# 10-RJ45_Protection.net
KiCad netlist of a schematic drawn in Altium Designer
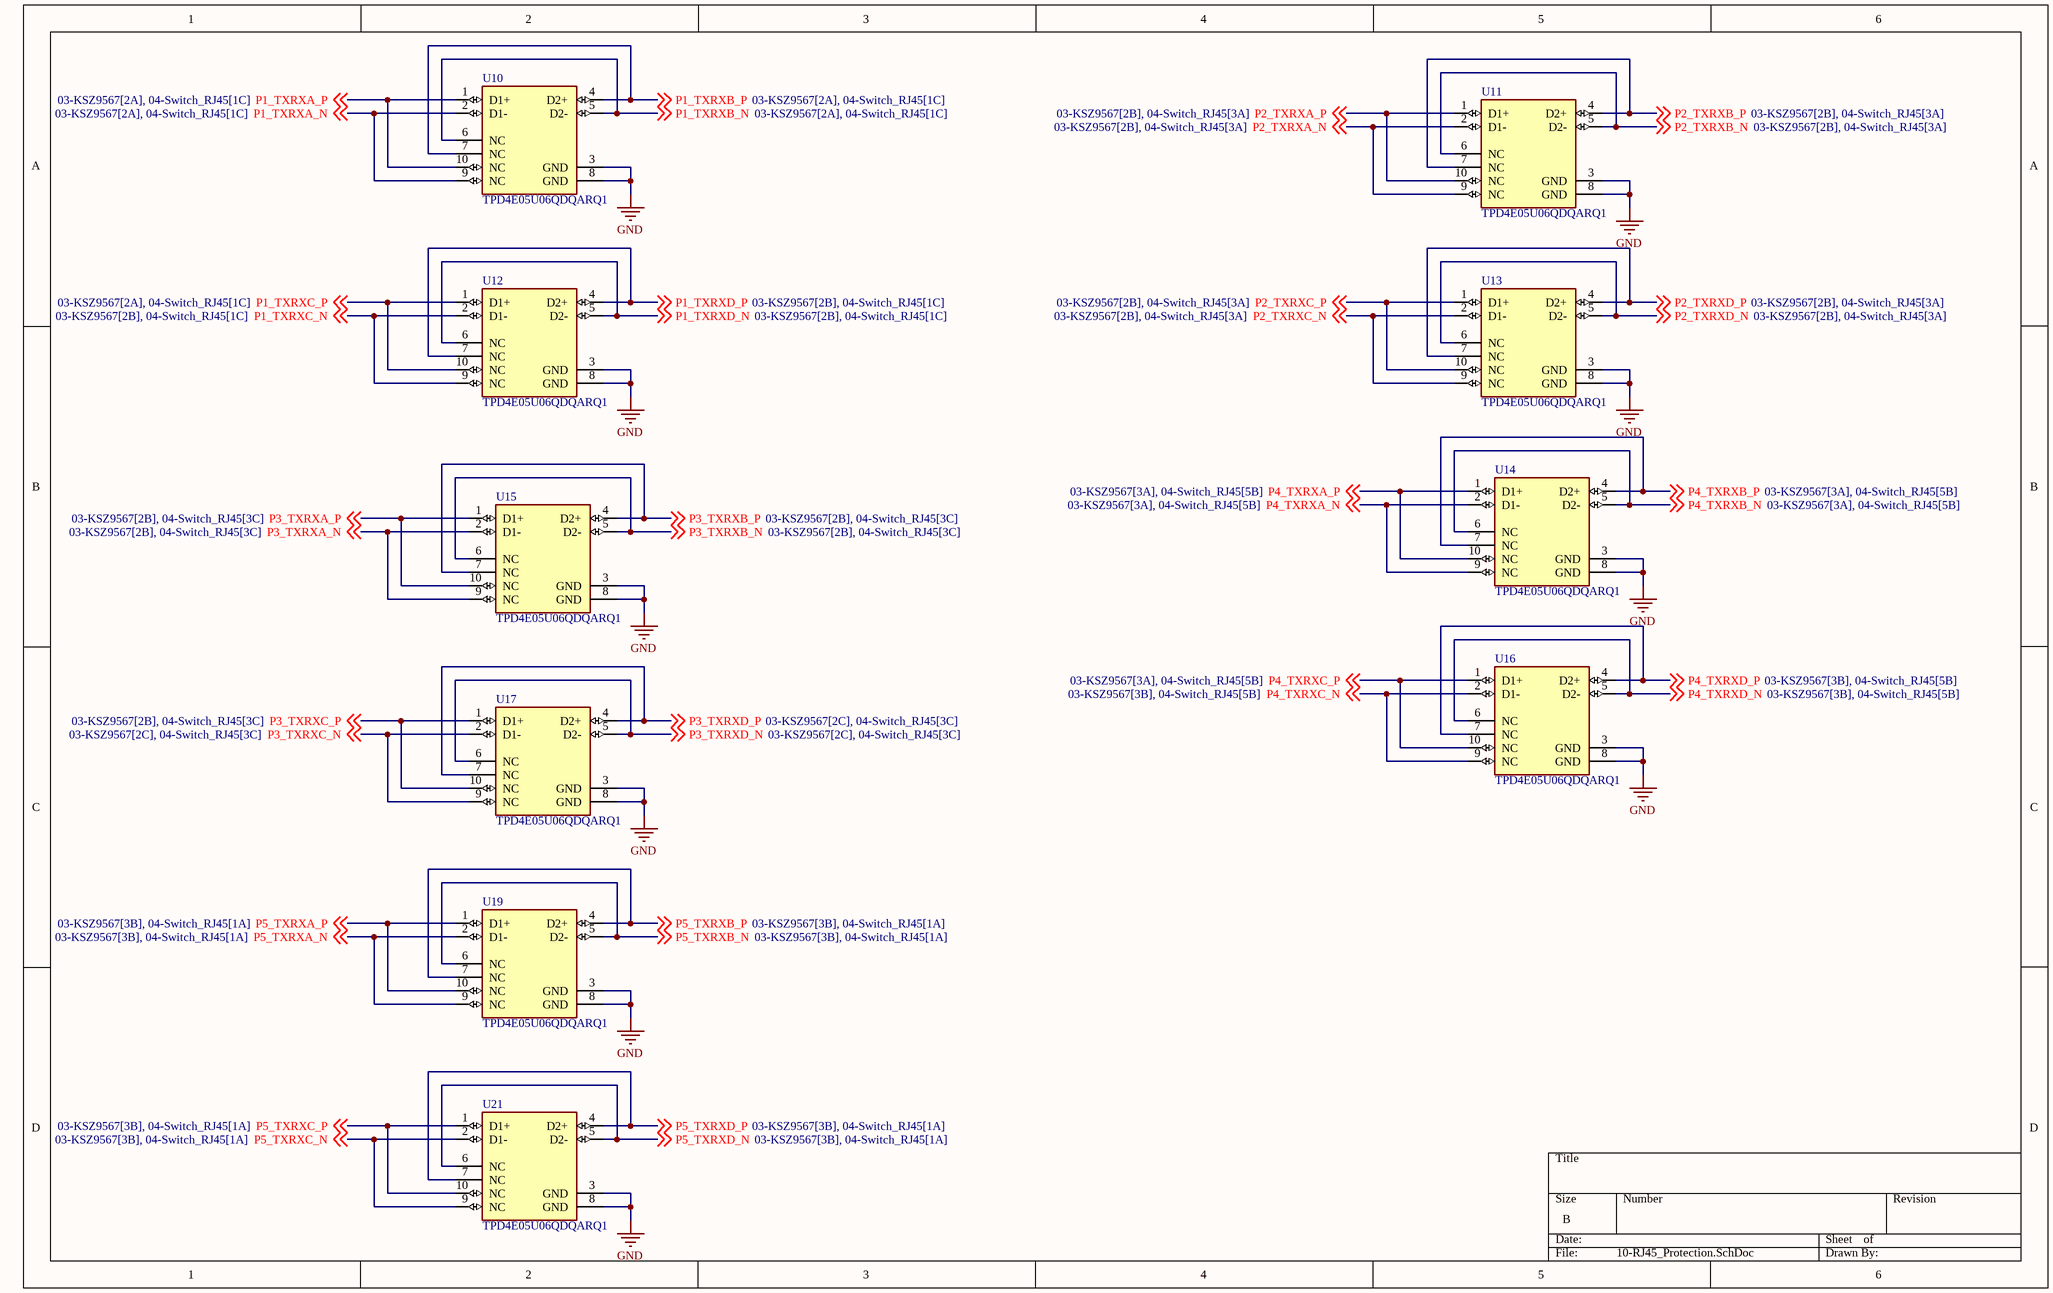
[diagram p0: 10-RJ45_Protection.SchDoc]

(export (version "E")
  (design (tool "Eeschema 10.0.6"))
  (components
    (comp (ref "U10")
      (value "TPD4E05U06QDQARQ1")
      (footprint "FP-DQA0010A-MFG")
      (description "TVS DIODE 5.5V 14V 10USON")
      (fields
        (field (name "OCTOPART") "https://octopart.com/tpd4e05u06qdqarq1-texas+instruments-48523459")
        (field (name "MANUFACTURER") "Texas Instruments")
      )
      (libsource (lib "Altium Content Vault") (part "f11f7ff102fa2b028e1355c732c836d"))
    )
    (comp (ref "U11")
      (value "TPD4E05U06QDQARQ1")
      (footprint "FP-DQA0010A-MFG")
      (description "TVS DIODE 5.5V 14V 10USON")
      (fields
        (field (name "OCTOPART") "https://octopart.com/tpd4e05u06qdqarq1-texas+instruments-48523459")
        (field (name "MANUFACTURER") "Texas Instruments")
      )
      (libsource (lib "Altium Content Vault") (part "f11f7ff102fa2b028e1355c732c836d"))
    )
    (comp (ref "U12")
      (value "TPD4E05U06QDQARQ1")
      (footprint "FP-DQA0010A-MFG")
      (description "TVS DIODE 5.5V 14V 10USON")
      (fields
        (field (name "OCTOPART") "https://octopart.com/tpd4e05u06qdqarq1-texas+instruments-48523459")
        (field (name "MANUFACTURER") "Texas Instruments")
      )
      (libsource (lib "Altium Content Vault") (part "f11f7ff102fa2b028e1355c732c836d"))
    )
    (comp (ref "U13")
      (value "TPD4E05U06QDQARQ1")
      (footprint "FP-DQA0010A-MFG")
      (description "TVS DIODE 5.5V 14V 10USON")
      (fields
        (field (name "OCTOPART") "https://octopart.com/tpd4e05u06qdqarq1-texas+instruments-48523459")
        (field (name "MANUFACTURER") "Texas Instruments")
      )
      (libsource (lib "Altium Content Vault") (part "f11f7ff102fa2b028e1355c732c836d"))
    )
    (comp (ref "U14")
      (value "TPD4E05U06QDQARQ1")
      (footprint "FP-DQA0010A-MFG")
      (description "TVS DIODE 5.5V 14V 10USON")
      (fields
        (field (name "OCTOPART") "https://octopart.com/tpd4e05u06qdqarq1-texas+instruments-48523459")
        (field (name "MANUFACTURER") "Texas Instruments")
      )
      (libsource (lib "Altium Content Vault") (part "f11f7ff102fa2b028e1355c732c836d"))
    )
    (comp (ref "U15")
      (value "TPD4E05U06QDQARQ1")
      (footprint "FP-DQA0010A-MFG")
      (description "TVS DIODE 5.5V 14V 10USON")
      (fields
        (field (name "OCTOPART") "https://octopart.com/tpd4e05u06qdqarq1-texas+instruments-48523459")
        (field (name "MANUFACTURER") "Texas Instruments")
      )
      (libsource (lib "Altium Content Vault") (part "f11f7ff102fa2b028e1355c732c836d"))
    )
    (comp (ref "U16")
      (value "TPD4E05U06QDQARQ1")
      (footprint "FP-DQA0010A-MFG")
      (description "TVS DIODE 5.5V 14V 10USON")
      (fields
        (field (name "OCTOPART") "https://octopart.com/tpd4e05u06qdqarq1-texas+instruments-48523459")
        (field (name "MANUFACTURER") "Texas Instruments")
      )
      (libsource (lib "Altium Content Vault") (part "f11f7ff102fa2b028e1355c732c836d"))
    )
    (comp (ref "U17")
      (value "TPD4E05U06QDQARQ1")
      (footprint "FP-DQA0010A-MFG")
      (description "TVS DIODE 5.5V 14V 10USON")
      (fields
        (field (name "OCTOPART") "https://octopart.com/tpd4e05u06qdqarq1-texas+instruments-48523459")
        (field (name "MANUFACTURER") "Texas Instruments")
      )
      (libsource (lib "Altium Content Vault") (part "f11f7ff102fa2b028e1355c732c836d"))
    )
    (comp (ref "U19")
      (value "TPD4E05U06QDQARQ1")
      (footprint "FP-DQA0010A-MFG")
      (description "TVS DIODE 5.5V 14V 10USON")
      (fields
        (field (name "OCTOPART") "https://octopart.com/tpd4e05u06qdqarq1-texas+instruments-48523459")
        (field (name "MANUFACTURER") "Texas Instruments")
      )
      (libsource (lib "Altium Content Vault") (part "f11f7ff102fa2b028e1355c732c836d"))
    )
    (comp (ref "U21")
      (value "TPD4E05U06QDQARQ1")
      (footprint "FP-DQA0010A-MFG")
      (description "TVS DIODE 5.5V 14V 10USON")
      (fields
        (field (name "OCTOPART") "https://octopart.com/tpd4e05u06qdqarq1-texas+instruments-48523459")
        (field (name "MANUFACTURER") "Texas Instruments")
      )
      (libsource (lib "Altium Content Vault") (part "f11f7ff102fa2b028e1355c732c836d"))
    )
  )
  (nets
    (net (code "1") (name "GND") (class "Default")
      (node (ref "U10") (pin "3") (pinfunction "GND_3") (pintype "power_in"))
      (node (ref "U10") (pin "8") (pinfunction "GND_8") (pintype "power_in"))
      (node (ref "U11") (pin "3") (pinfunction "GND_3") (pintype "power_in"))
      (node (ref "U11") (pin "8") (pinfunction "GND_8") (pintype "power_in"))
      (node (ref "U12") (pin "3") (pinfunction "GND_3") (pintype "power_in"))
      (node (ref "U12") (pin "8") (pinfunction "GND_8") (pintype "power_in"))
      (node (ref "U13") (pin "3") (pinfunction "GND_3") (pintype "power_in"))
      (node (ref "U13") (pin "8") (pinfunction "GND_8") (pintype "power_in"))
      (node (ref "U14") (pin "3") (pinfunction "GND_3") (pintype "power_in"))
      (node (ref "U14") (pin "8") (pinfunction "GND_8") (pintype "power_in"))
      (node (ref "U15") (pin "3") (pinfunction "GND_3") (pintype "power_in"))
      (node (ref "U15") (pin "8") (pinfunction "GND_8") (pintype "power_in"))
      (node (ref "U16") (pin "3") (pinfunction "GND_3") (pintype "power_in"))
      (node (ref "U16") (pin "8") (pinfunction "GND_8") (pintype "power_in"))
      (node (ref "U17") (pin "3") (pinfunction "GND_3") (pintype "power_in"))
      (node (ref "U17") (pin "8") (pinfunction "GND_8") (pintype "power_in"))
      (node (ref "U19") (pin "3") (pinfunction "GND_3") (pintype "power_in"))
      (node (ref "U19") (pin "8") (pinfunction "GND_8") (pintype "power_in"))
      (node (ref "U21") (pin "3") (pinfunction "GND_3") (pintype "power_in"))
      (node (ref "U21") (pin "8") (pinfunction "GND_8") (pintype "power_in"))
    )
    (net (code "2") (name "P1_TXRXA_N") (class "Default")
      (node (ref "U10") (pin "2") (pinfunction "D1-_2") (pintype "bidirectional"))
      (node (ref "U10") (pin "9") (pinfunction "NC_9") (pintype "bidirectional"))
    )
    (net (code "3") (name "P1_TXRXA_P") (class "Default")
      (node (ref "U10") (pin "1") (pinfunction "D1+_1") (pintype "bidirectional"))
      (node (ref "U10") (pin "10") (pinfunction "NC_10") (pintype "bidirectional"))
    )
    (net (code "4") (name "P1_TXRXB_N") (class "Default")
      (node (ref "U10") (pin "5") (pinfunction "D2-_5") (pintype "bidirectional"))
      (node (ref "U10") (pin "6") (pinfunction "NC_6") (pintype "passive"))
    )
    (net (code "5") (name "P1_TXRXB_P") (class "Default")
      (node (ref "U10") (pin "4") (pinfunction "D2+_4") (pintype "bidirectional"))
      (node (ref "U10") (pin "7") (pinfunction "NC_7") (pintype "passive"))
    )
    (net (code "6") (name "P1_TXRXC_N") (class "Default")
      (node (ref "U12") (pin "2") (pinfunction "D1-_2") (pintype "bidirectional"))
      (node (ref "U12") (pin "9") (pinfunction "NC_9") (pintype "bidirectional"))
    )
    (net (code "7") (name "P1_TXRXC_P") (class "Default")
      (node (ref "U12") (pin "1") (pinfunction "D1+_1") (pintype "bidirectional"))
      (node (ref "U12") (pin "10") (pinfunction "NC_10") (pintype "bidirectional"))
    )
    (net (code "8") (name "P1_TXRXD_N") (class "Default")
      (node (ref "U12") (pin "5") (pinfunction "D2-_5") (pintype "bidirectional"))
      (node (ref "U12") (pin "6") (pinfunction "NC_6") (pintype "passive"))
    )
    (net (code "9") (name "P1_TXRXD_P") (class "Default")
      (node (ref "U12") (pin "4") (pinfunction "D2+_4") (pintype "bidirectional"))
      (node (ref "U12") (pin "7") (pinfunction "NC_7") (pintype "passive"))
    )
    (net (code "10") (name "P2_TXRXA_N") (class "Default")
      (node (ref "U11") (pin "2") (pinfunction "D1-_2") (pintype "bidirectional"))
      (node (ref "U11") (pin "9") (pinfunction "NC_9") (pintype "bidirectional"))
    )
    (net (code "11") (name "P2_TXRXA_P") (class "Default")
      (node (ref "U11") (pin "1") (pinfunction "D1+_1") (pintype "bidirectional"))
      (node (ref "U11") (pin "10") (pinfunction "NC_10") (pintype "bidirectional"))
    )
    (net (code "12") (name "P2_TXRXB_N") (class "Default")
      (node (ref "U11") (pin "5") (pinfunction "D2-_5") (pintype "bidirectional"))
      (node (ref "U11") (pin "6") (pinfunction "NC_6") (pintype "passive"))
    )
    (net (code "13") (name "P2_TXRXB_P") (class "Default")
      (node (ref "U11") (pin "4") (pinfunction "D2+_4") (pintype "bidirectional"))
      (node (ref "U11") (pin "7") (pinfunction "NC_7") (pintype "passive"))
    )
    (net (code "14") (name "P2_TXRXC_N") (class "Default")
      (node (ref "U13") (pin "2") (pinfunction "D1-_2") (pintype "bidirectional"))
      (node (ref "U13") (pin "9") (pinfunction "NC_9") (pintype "bidirectional"))
    )
    (net (code "15") (name "P2_TXRXC_P") (class "Default")
      (node (ref "U13") (pin "1") (pinfunction "D1+_1") (pintype "bidirectional"))
      (node (ref "U13") (pin "10") (pinfunction "NC_10") (pintype "bidirectional"))
    )
    (net (code "16") (name "P2_TXRXD_N") (class "Default")
      (node (ref "U13") (pin "5") (pinfunction "D2-_5") (pintype "bidirectional"))
      (node (ref "U13") (pin "6") (pinfunction "NC_6") (pintype "passive"))
    )
    (net (code "17") (name "P2_TXRXD_P") (class "Default")
      (node (ref "U13") (pin "4") (pinfunction "D2+_4") (pintype "bidirectional"))
      (node (ref "U13") (pin "7") (pinfunction "NC_7") (pintype "passive"))
    )
    (net (code "18") (name "P3_TXRXA_N") (class "Default")
      (node (ref "U15") (pin "2") (pinfunction "D1-_2") (pintype "bidirectional"))
      (node (ref "U15") (pin "9") (pinfunction "NC_9") (pintype "bidirectional"))
    )
    (net (code "19") (name "P3_TXRXA_P") (class "Default")
      (node (ref "U15") (pin "1") (pinfunction "D1+_1") (pintype "bidirectional"))
      (node (ref "U15") (pin "10") (pinfunction "NC_10") (pintype "bidirectional"))
    )
    (net (code "20") (name "P3_TXRXB_N") (class "Default")
      (node (ref "U15") (pin "5") (pinfunction "D2-_5") (pintype "bidirectional"))
      (node (ref "U15") (pin "6") (pinfunction "NC_6") (pintype "passive"))
    )
    (net (code "21") (name "P3_TXRXB_P") (class "Default")
      (node (ref "U15") (pin "4") (pinfunction "D2+_4") (pintype "bidirectional"))
      (node (ref "U15") (pin "7") (pinfunction "NC_7") (pintype "passive"))
    )
    (net (code "22") (name "P3_TXRXC_N") (class "Default")
      (node (ref "U17") (pin "2") (pinfunction "D1-_2") (pintype "bidirectional"))
      (node (ref "U17") (pin "9") (pinfunction "NC_9") (pintype "bidirectional"))
    )
    (net (code "23") (name "P3_TXRXC_P") (class "Default")
      (node (ref "U17") (pin "1") (pinfunction "D1+_1") (pintype "bidirectional"))
      (node (ref "U17") (pin "10") (pinfunction "NC_10") (pintype "bidirectional"))
    )
    (net (code "24") (name "P3_TXRXD_N") (class "Default")
      (node (ref "U17") (pin "5") (pinfunction "D2-_5") (pintype "bidirectional"))
      (node (ref "U17") (pin "6") (pinfunction "NC_6") (pintype "passive"))
    )
    (net (code "25") (name "P3_TXRXD_P") (class "Default")
      (node (ref "U17") (pin "4") (pinfunction "D2+_4") (pintype "bidirectional"))
      (node (ref "U17") (pin "7") (pinfunction "NC_7") (pintype "passive"))
    )
    (net (code "26") (name "P4_TXRXA_N") (class "Default")
      (node (ref "U14") (pin "2") (pinfunction "D1-_2") (pintype "bidirectional"))
      (node (ref "U14") (pin "9") (pinfunction "NC_9") (pintype "bidirectional"))
    )
    (net (code "27") (name "P4_TXRXA_P") (class "Default")
      (node (ref "U14") (pin "1") (pinfunction "D1+_1") (pintype "bidirectional"))
      (node (ref "U14") (pin "10") (pinfunction "NC_10") (pintype "bidirectional"))
    )
    (net (code "28") (name "P4_TXRXB_N") (class "Default")
      (node (ref "U14") (pin "5") (pinfunction "D2-_5") (pintype "bidirectional"))
      (node (ref "U14") (pin "6") (pinfunction "NC_6") (pintype "passive"))
    )
    (net (code "29") (name "P4_TXRXB_P") (class "Default")
      (node (ref "U14") (pin "4") (pinfunction "D2+_4") (pintype "bidirectional"))
      (node (ref "U14") (pin "7") (pinfunction "NC_7") (pintype "passive"))
    )
    (net (code "30") (name "P4_TXRXC_N") (class "Default")
      (node (ref "U16") (pin "2") (pinfunction "D1-_2") (pintype "bidirectional"))
      (node (ref "U16") (pin "9") (pinfunction "NC_9") (pintype "bidirectional"))
    )
    (net (code "31") (name "P4_TXRXC_P") (class "Default")
      (node (ref "U16") (pin "1") (pinfunction "D1+_1") (pintype "bidirectional"))
      (node (ref "U16") (pin "10") (pinfunction "NC_10") (pintype "bidirectional"))
    )
    (net (code "32") (name "P4_TXRXD_N") (class "Default")
      (node (ref "U16") (pin "5") (pinfunction "D2-_5") (pintype "bidirectional"))
      (node (ref "U16") (pin "6") (pinfunction "NC_6") (pintype "passive"))
    )
    (net (code "33") (name "P4_TXRXD_P") (class "Default")
      (node (ref "U16") (pin "4") (pinfunction "D2+_4") (pintype "bidirectional"))
      (node (ref "U16") (pin "7") (pinfunction "NC_7") (pintype "passive"))
    )
    (net (code "34") (name "P5_TXRXA_N") (class "Default")
      (node (ref "U19") (pin "2") (pinfunction "D1-_2") (pintype "bidirectional"))
      (node (ref "U19") (pin "9") (pinfunction "NC_9") (pintype "bidirectional"))
    )
    (net (code "35") (name "P5_TXRXA_P") (class "Default")
      (node (ref "U19") (pin "1") (pinfunction "D1+_1") (pintype "bidirectional"))
      (node (ref "U19") (pin "10") (pinfunction "NC_10") (pintype "bidirectional"))
    )
    (net (code "36") (name "P5_TXRXB_N") (class "Default")
      (node (ref "U19") (pin "5") (pinfunction "D2-_5") (pintype "bidirectional"))
      (node (ref "U19") (pin "6") (pinfunction "NC_6") (pintype "passive"))
    )
    (net (code "37") (name "P5_TXRXB_P") (class "Default")
      (node (ref "U19") (pin "4") (pinfunction "D2+_4") (pintype "bidirectional"))
      (node (ref "U19") (pin "7") (pinfunction "NC_7") (pintype "passive"))
    )
    (net (code "38") (name "P5_TXRXC_N") (class "Default")
      (node (ref "U21") (pin "2") (pinfunction "D1-_2") (pintype "bidirectional"))
      (node (ref "U21") (pin "9") (pinfunction "NC_9") (pintype "bidirectional"))
    )
    (net (code "39") (name "P5_TXRXC_P") (class "Default")
      (node (ref "U21") (pin "1") (pinfunction "D1+_1") (pintype "bidirectional"))
      (node (ref "U21") (pin "10") (pinfunction "NC_10") (pintype "bidirectional"))
    )
    (net (code "40") (name "P5_TXRXD_N") (class "Default")
      (node (ref "U21") (pin "5") (pinfunction "D2-_5") (pintype "bidirectional"))
      (node (ref "U21") (pin "6") (pinfunction "NC_6") (pintype "passive"))
    )
    (net (code "41") (name "P5_TXRXD_P") (class "Default")
      (node (ref "U21") (pin "4") (pinfunction "D2+_4") (pintype "bidirectional"))
      (node (ref "U21") (pin "7") (pinfunction "NC_7") (pintype "passive"))
    )
  )
)
